# ir-duplicator.net
KiCad netlist of a schematic drawn in EAGLE
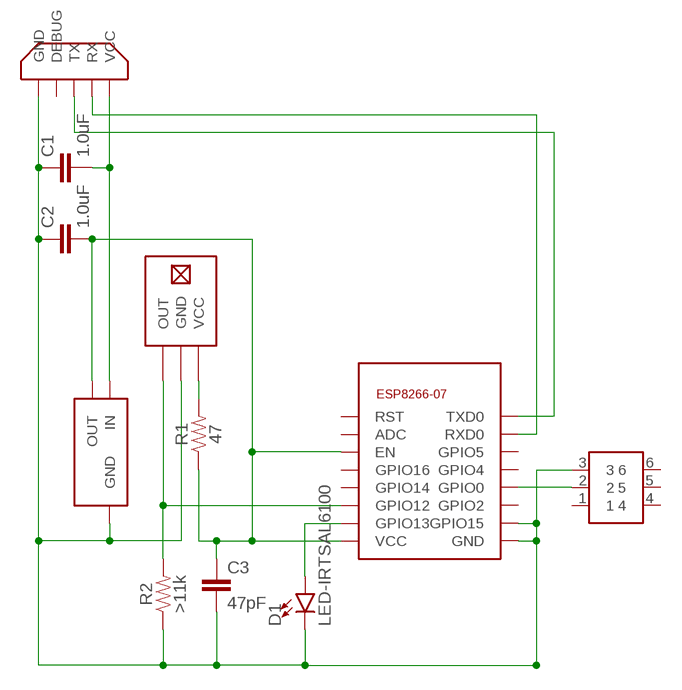
[diagram p0: schematic, sheet 1]

(export (version "E")
  (design (tool "Eeschema 10.0.6"))
  (components
    (comp (ref "C1")
      (value "1.0uF")
      (footprint "eagle-import:0805")
      (libsource (lib "eagle-import") (part "1.0UF-0805-25V-10%"))
    )
    (comp (ref "C2")
      (value "1.0uF")
      (footprint "eagle-import:0805")
      (libsource (lib "eagle-import") (part "1.0UF-0805-25V-10%"))
    )
    (comp (ref "C3")
      (value "47pF")
      (footprint "eagle-import:0603")
      (libsource (lib "eagle-import") (part "47PF-0603-50V-5%"))
    )
    (comp (ref "D1")
      (value "LED-IRTSAL6100")
      (footprint "eagle-import:LED_5MM")
      (libsource (lib "eagle-import") (part "LED-IRTSAL6100"))
    )
    (comp (ref "R1")
      (value "47")
      (footprint "eagle-import:0603")
      (libsource (lib "eagle-import") (part "0OHM-0603-1/10W-5%"))
    )
    (comp (ref "R2")
      (value ">11k")
      (footprint "eagle-import:0603")
      (libsource (lib "eagle-import") (part "10KOHM-0603-1/10W-1%"))
    )
    (comp (ref "U$1")
      (value "AX-1838HSHORIZ")
      (footprint "eagle-import:AX-1838HS-HORIZ")
      (libsource (lib "eagle-import") (part "AX-1838HSHORIZ"))
    )
    (comp (ref "U$2")
      (value "ESP8266-07SMD")
      (footprint "eagle-import:ESP8266-07")
      (libsource (lib "eagle-import") (part "ESP8266-07SMD"))
    )
    (comp (ref "U$3")
      (value "AYZ0202AGRL")
      (footprint "eagle-import:AYZ0202AGRL")
      (libsource (lib "eagle-import") (part "AYZ0202AGRL"))
    )
    (comp (ref "U$4")
      (value "MICROUSB609-4613-1-ND")
      (footprint "eagle-import:MICROUSB")
      (libsource (lib "eagle-import") (part "MICROUSB609-4613-1-ND"))
    )
    (comp (ref "U$5")
      (value "AZ1117E")
      (footprint "eagle-import:SOT-223")
      (libsource (lib "eagle-import") (part "AZ1117E"))
    )
  )
  (nets
    (net (code "1") (name "Net-(C2-Pad2)") (class "Default")
      (node (ref "C2") (pin "2") (pinfunction "2_2") (pintype "passive"))
      (node (ref "C3") (pin "1") (pinfunction "1_1") (pintype "passive"))
      (node (ref "R1") (pin "1") (pinfunction "1_1") (pintype "passive"))
      (node (ref "U$2") (pin "EN") (pinfunction "EN_EN") (pintype "input"))
      (node (ref "U$2") (pin "VCC") (pinfunction "VCC_VCC") (pintype "power_in"))
      (node (ref "U$5") (pin "P$1") (pinfunction "OUT_P$1") (pintype "output"))
      (node (ref "U$5") (pin "P$2") (pinfunction "OUT_P$2") (pintype "output"))
    )
    (net (code "2") (name "Net-(D1-C)") (class "Default")
      (node (ref "C1") (pin "1") (pinfunction "1_1") (pintype "passive"))
      (node (ref "C2") (pin "1") (pinfunction "1_1") (pintype "passive"))
      (node (ref "C3") (pin "2") (pinfunction "2_2") (pintype "passive"))
      (node (ref "D1") (pin "K") (pinfunction "C_K") (pintype "passive"))
      (node (ref "R2") (pin "1") (pinfunction "1_1") (pintype "passive"))
      (node (ref "U$1") (pin "GND") (pinfunction "GND_GND") (pintype "power_in"))
      (node (ref "U$2") (pin "GND") (pinfunction "GND_GND") (pintype "power_in"))
      (node (ref "U$2") (pin "GPIO15") (pinfunction "GPIO15_GPIO15") (pintype "bidirectional"))
      (node (ref "U$3") (pin "3") (pinfunction "3_3") (pintype "bidirectional"))
      (node (ref "U$4") (pin "GND") (pinfunction "GND_GND") (pintype "power_in"))
      (node (ref "U$5") (pin "P$3") (pinfunction "GND_P$3") (pintype "power_in"))
    )
    (net (code "3") (name "Net-(D1-PadA)") (class "Default")
      (node (ref "D1") (pin "A") (pinfunction "A_A") (pintype "passive"))
      (node (ref "U$2") (pin "GPIO13") (pinfunction "GPIO13_GPIO13") (pintype "bidirectional"))
    )
    (net (code "4") (name "Net-(R1-Pad2)") (class "Default")
      (node (ref "R1") (pin "2") (pinfunction "2_2") (pintype "passive"))
      (node (ref "U$1") (pin "VCC") (pinfunction "VCC_VCC") (pintype "power_in"))
    )
    (net (code "5") (name "Net-(R2-Pad2)") (class "Default")
      (node (ref "R2") (pin "2") (pinfunction "2_2") (pintype "passive"))
      (node (ref "U$1") (pin "OUT") (pinfunction "OUT_OUT") (pintype "bidirectional"))
      (node (ref "U$2") (pin "GPIO12") (pinfunction "GPIO12_GPIO12") (pintype "bidirectional"))
    )
    (net (code "6") (name "Net-(U$2-PadGPIO0)") (class "Default")
      (node (ref "U$2") (pin "GPIO0") (pinfunction "GPIO0_GPIO0") (pintype "bidirectional"))
      (node (ref "U$3") (pin "2") (pinfunction "2_2") (pintype "bidirectional"))
    )
    (net (code "7") (name "Net-(U$2-PadRXD0)") (class "Default")
      (node (ref "U$2") (pin "RXD0") (pinfunction "RXD0_RXD0") (pintype "bidirectional"))
      (node (ref "U$4") (pin "RX") (pinfunction "RX_RX") (pintype "bidirectional"))
    )
    (net (code "8") (name "Net-(U$2-PadTXD0)") (class "Default")
      (node (ref "U$2") (pin "TXD0") (pinfunction "TXD0_TXD0") (pintype "bidirectional"))
      (node (ref "U$4") (pin "TX") (pinfunction "TX_TX") (pintype "bidirectional"))
    )
    (net (code "9") (name "Net-(U$5-IN)") (class "Default")
      (node (ref "C1") (pin "2") (pinfunction "2_2") (pintype "passive"))
      (node (ref "U$4") (pin "VCC") (pinfunction "VCC_VCC") (pintype "power_in"))
      (node (ref "U$5") (pin "P$4") (pinfunction "IN_P$4") (pintype "input"))
    )
    (net (code "10") (name "unconnected-(U$2-PadADC)") (class "Default")
      (node (ref "U$2") (pin "ADC") (pinfunction "ADC_ADC") (pintype "input"))
    )
    (net (code "11") (name "unconnected-(U$2-PadGPIO2)") (class "Default")
      (node (ref "U$2") (pin "GPIO2") (pinfunction "GPIO2_GPIO2") (pintype "bidirectional"))
    )
    (net (code "12") (name "unconnected-(U$2-PadGPIO4)") (class "Default")
      (node (ref "U$2") (pin "GPIO4") (pinfunction "GPIO4_GPIO4") (pintype "bidirectional"))
    )
    (net (code "13") (name "unconnected-(U$2-PadGPIO5)") (class "Default")
      (node (ref "U$2") (pin "GPIO5") (pinfunction "GPIO5_GPIO5") (pintype "bidirectional"))
    )
    (net (code "14") (name "unconnected-(U$2-PadGPIO14)") (class "Default")
      (node (ref "U$2") (pin "GPIO14") (pinfunction "GPIO14_GPIO14") (pintype "bidirectional"))
    )
    (net (code "15") (name "unconnected-(U$2-PadGPIO16)") (class "Default")
      (node (ref "U$2") (pin "GPIO16") (pinfunction "GPIO16_GPIO16") (pintype "bidirectional"))
    )
    (net (code "16") (name "unconnected-(U$2-PadRST)") (class "Default")
      (node (ref "U$2") (pin "RST") (pinfunction "RST_RST") (pintype "input"))
    )
    (net (code "17") (name "unconnected-(U$3-Pad1)") (class "Default")
      (node (ref "U$3") (pin "1") (pinfunction "1_1") (pintype "bidirectional"))
    )
    (net (code "18") (name "unconnected-(U$3-Pad4)") (class "Default")
      (node (ref "U$3") (pin "4") (pinfunction "4_4") (pintype "bidirectional"))
    )
    (net (code "19") (name "unconnected-(U$3-Pad5)") (class "Default")
      (node (ref "U$3") (pin "5") (pinfunction "5_5") (pintype "bidirectional"))
    )
    (net (code "20") (name "unconnected-(U$3-Pad6)") (class "Default")
      (node (ref "U$3") (pin "6") (pinfunction "6_6") (pintype "bidirectional"))
    )
    (net (code "21") (name "unconnected-(U$4-PadDEBUG)") (class "Default")
      (node (ref "U$4") (pin "DEBUG") (pinfunction "DEBUG_DEBUG") (pintype "bidirectional"))
    )
  )
)
